# kitt.net
KiCad netlist of a schematic drawn in EAGLE
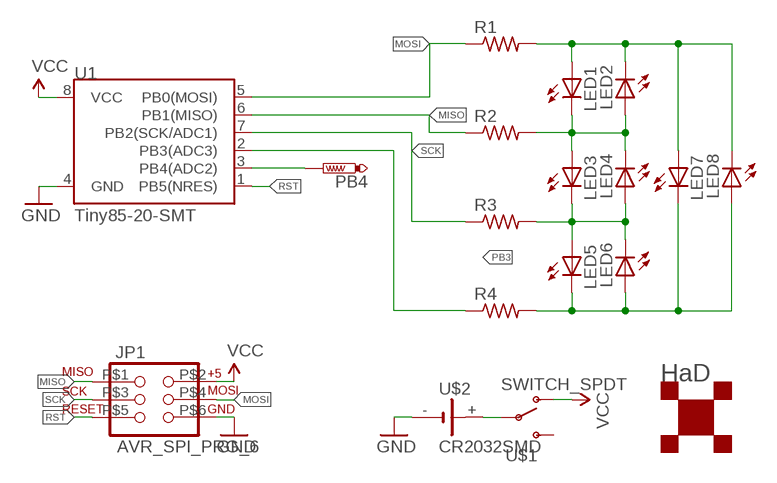
[diagram p0: schematic, sheet 1]

(export (version "E")
  (design (tool "Eeschema 10.0.6"))
  (components
    (comp (ref "JP1")
      (value "AVR_SPI_PRG_6")
      (footprint "eagle-import:2X3_SMD_PAD")
      (libsource (lib "eagle-import") (part "AVR_SPI_PRG_6"))
    )
    (comp (ref "LED1")
      (value "LEDCHIPLED-0603-TTW")
      (footprint "eagle-import:CHIPLED-0603-TTW")
      (libsource (lib "eagle-import") (part "LEDCHIPLED-0603-TTW"))
    )
    (comp (ref "LED2")
      (value "LEDCHIPLED-0603-TTW")
      (footprint "eagle-import:CHIPLED-0603-TTW")
      (libsource (lib "eagle-import") (part "LEDCHIPLED-0603-TTW"))
    )
    (comp (ref "LED3")
      (value "LEDCHIPLED-0603-TTW")
      (footprint "eagle-import:CHIPLED-0603-TTW")
      (libsource (lib "eagle-import") (part "LEDCHIPLED-0603-TTW"))
    )
    (comp (ref "LED4")
      (value "LEDCHIPLED-0603-TTW")
      (footprint "eagle-import:CHIPLED-0603-TTW")
      (libsource (lib "eagle-import") (part "LEDCHIPLED-0603-TTW"))
    )
    (comp (ref "LED5")
      (value "LEDCHIPLED-0603-TTW")
      (footprint "eagle-import:CHIPLED-0603-TTW")
      (libsource (lib "eagle-import") (part "LEDCHIPLED-0603-TTW"))
    )
    (comp (ref "LED6")
      (value "LEDCHIPLED-0603-TTW")
      (footprint "eagle-import:CHIPLED-0603-TTW")
      (libsource (lib "eagle-import") (part "LEDCHIPLED-0603-TTW"))
    )
    (comp (ref "LED7")
      (value "LEDCHIPLED-0603-TTW")
      (footprint "eagle-import:CHIPLED-0603-TTW")
      (libsource (lib "eagle-import") (part "LEDCHIPLED-0603-TTW"))
    )
    (comp (ref "LED8")
      (value "LEDCHIPLED-0603-TTW")
      (footprint "eagle-import:CHIPLED-0603-TTW")
      (libsource (lib "eagle-import") (part "LEDCHIPLED-0603-TTW"))
    )
    (comp (ref "PB4")
      (value "PTR1B1,27")
      (footprint "eagle-import:B1,27")
      (libsource (lib "eagle-import") (part "PTR1B1,27"))
    )
    (comp (ref "R1")
      (value "R-US_R0603")
      (footprint "eagle-import:R0603")
      (libsource (lib "eagle-import") (part "R-US_R0603"))
    )
    (comp (ref "R2")
      (value "R-US_R0603")
      (footprint "eagle-import:R0603")
      (libsource (lib "eagle-import") (part "R-US_R0603"))
    )
    (comp (ref "R3")
      (value "R-US_R0603")
      (footprint "eagle-import:R0603")
      (libsource (lib "eagle-import") (part "R-US_R0603"))
    )
    (comp (ref "R4")
      (value "R-US_R0603")
      (footprint "eagle-import:R0603")
      (libsource (lib "eagle-import") (part "R-US_R0603"))
    )
    (comp (ref "U$1")
      (value "SWITCH_SPDT")
      (footprint "eagle-import:KPS-1290")
      (libsource (lib "eagle-import") (part "SWITCH_SPDT"))
    )
    (comp (ref "U$2")
      (value "CR2032SMD")
      (footprint "eagle-import:CR2032SMD")
      (libsource (lib "eagle-import") (part "CR2032SMD"))
    )
    (comp (ref "U$3")
      (value "HACKADAY_1CM")
      (footprint "eagle-import:HACKADAY_LOGO")
      (libsource (lib "eagle-import") (part "HACKADAY_1CM"))
    )
    (comp (ref "U1")
      (value "Tiny85-20-SMT")
      (footprint "eagle-import:SO08-EIAJ")
      (libsource (lib "eagle-import") (part "ATTINY45TINY85-20-SMT"))
    )
  )
  (nets
    (net (code "1") (name "GND") (class "Default")
      (node (ref "JP1") (pin "P$6") (pinfunction "6_P$6") (pintype "passive"))
      (node (ref "U$2") (pin "-") (pinfunction "-_-") (pintype "passive"))
      (node (ref "U1") (pin "4") (pinfunction "GND_4") (pintype "bidirectional"))
    )
    (net (code "2") (name "MISO") (class "Default")
      (node (ref "JP1") (pin "P$1") (pinfunction "1_P$1") (pintype "passive"))
      (node (ref "R2") (pin "1") (pinfunction "1_1") (pintype "passive"))
      (node (ref "U1") (pin "6") (pinfunction "PB1(MISO)_6") (pintype "bidirectional"))
    )
    (net (code "3") (name "MOSI") (class "Default")
      (node (ref "JP1") (pin "P$4") (pinfunction "4_P$4") (pintype "passive"))
      (node (ref "R1") (pin "1") (pinfunction "1_1") (pintype "passive"))
      (node (ref "U1") (pin "5") (pinfunction "PB0(MOSI)_5") (pintype "bidirectional"))
    )
    (net (code "4") (name "Net-(LED1-A)") (class "Default")
      (node (ref "LED1") (pin "A@1") (pinfunction "A_A@1") (pintype "passive"))
      (node (ref "LED2") (pin "C@1") (pinfunction "C_C@1") (pintype "passive"))
      (node (ref "LED7") (pin "A@1") (pinfunction "A_A@1") (pintype "passive"))
      (node (ref "LED8") (pin "C@1") (pinfunction "C_C@1") (pintype "passive"))
      (node (ref "R1") (pin "2") (pinfunction "2_2") (pintype "passive"))
    )
    (net (code "5") (name "Net-(LED1-C)") (class "Default")
      (node (ref "LED1") (pin "C@1") (pinfunction "C_C@1") (pintype "passive"))
      (node (ref "LED2") (pin "A@1") (pinfunction "A_A@1") (pintype "passive"))
      (node (ref "LED3") (pin "A@1") (pinfunction "A_A@1") (pintype "passive"))
      (node (ref "LED4") (pin "C@1") (pinfunction "C_C@1") (pintype "passive"))
      (node (ref "R2") (pin "2") (pinfunction "2_2") (pintype "passive"))
    )
    (net (code "6") (name "Net-(LED3-C)") (class "Default")
      (node (ref "LED3") (pin "C@1") (pinfunction "C_C@1") (pintype "passive"))
      (node (ref "LED4") (pin "A@1") (pinfunction "A_A@1") (pintype "passive"))
      (node (ref "LED5") (pin "A@1") (pinfunction "A_A@1") (pintype "passive"))
      (node (ref "LED6") (pin "C@1") (pinfunction "C_C@1") (pintype "passive"))
      (node (ref "R3") (pin "2") (pinfunction "2_2") (pintype "passive"))
    )
    (net (code "7") (name "Net-(LED5-C)") (class "Default")
      (node (ref "LED5") (pin "C@1") (pinfunction "C_C@1") (pintype "passive"))
      (node (ref "LED6") (pin "A@1") (pinfunction "A_A@1") (pintype "passive"))
      (node (ref "LED7") (pin "C@1") (pinfunction "C_C@1") (pintype "passive"))
      (node (ref "LED8") (pin "A@1") (pinfunction "A_A@1") (pintype "passive"))
      (node (ref "R4") (pin "2") (pinfunction "2_2") (pintype "passive"))
    )
    (net (code "8") (name "Net-(U$1-PadP)") (class "Default")
      (node (ref "U$1") (pin "P") (pinfunction "P_P") (pintype "passive"))
      (node (ref "U$2") (pin "+") (pinfunction "+_+") (pintype "passive"))
    )
    (net (code "9") (name "Net-(U1-PB4(ADC2))") (class "Default")
      (node (ref "PB4") (pin "TP") (pinfunction "TP_TP") (pintype "input"))
      (node (ref "U1") (pin "3") (pinfunction "PB4(ADC2)_3") (pintype "bidirectional"))
    )
    (net (code "10") (name "PB3") (class "Default")
      (node (ref "R4") (pin "1") (pinfunction "1_1") (pintype "passive"))
      (node (ref "U1") (pin "2") (pinfunction "PB3(ADC3)_2") (pintype "bidirectional"))
    )
    (net (code "11") (name "RST") (class "Default")
      (node (ref "JP1") (pin "P$5") (pinfunction "5_P$5") (pintype "passive"))
      (node (ref "U1") (pin "1") (pinfunction "PB5(NRES)_1") (pintype "bidirectional"))
    )
    (net (code "12") (name "SCK") (class "Default")
      (node (ref "JP1") (pin "P$3") (pinfunction "3_P$3") (pintype "passive"))
      (node (ref "R3") (pin "1") (pinfunction "1_1") (pintype "passive"))
      (node (ref "U1") (pin "7") (pinfunction "PB2(SCK/ADC1)_7") (pintype "bidirectional"))
    )
    (net (code "13") (name "VCC") (class "Default")
      (node (ref "JP1") (pin "P$2") (pinfunction "2_P$2") (pintype "passive"))
      (node (ref "U$1") (pin "O") (pinfunction "O_O") (pintype "passive"))
      (node (ref "U1") (pin "8") (pinfunction "VCC_8") (pintype "bidirectional"))
    )
    (net (code "14") (name "unconnected-(U$1-PadS)") (class "Default")
      (node (ref "U$1") (pin "S") (pinfunction "S_S") (pintype "passive"))
    )
  )
)
